# connect.net
KiCad netlist of a schematic drawn in Altium Designer
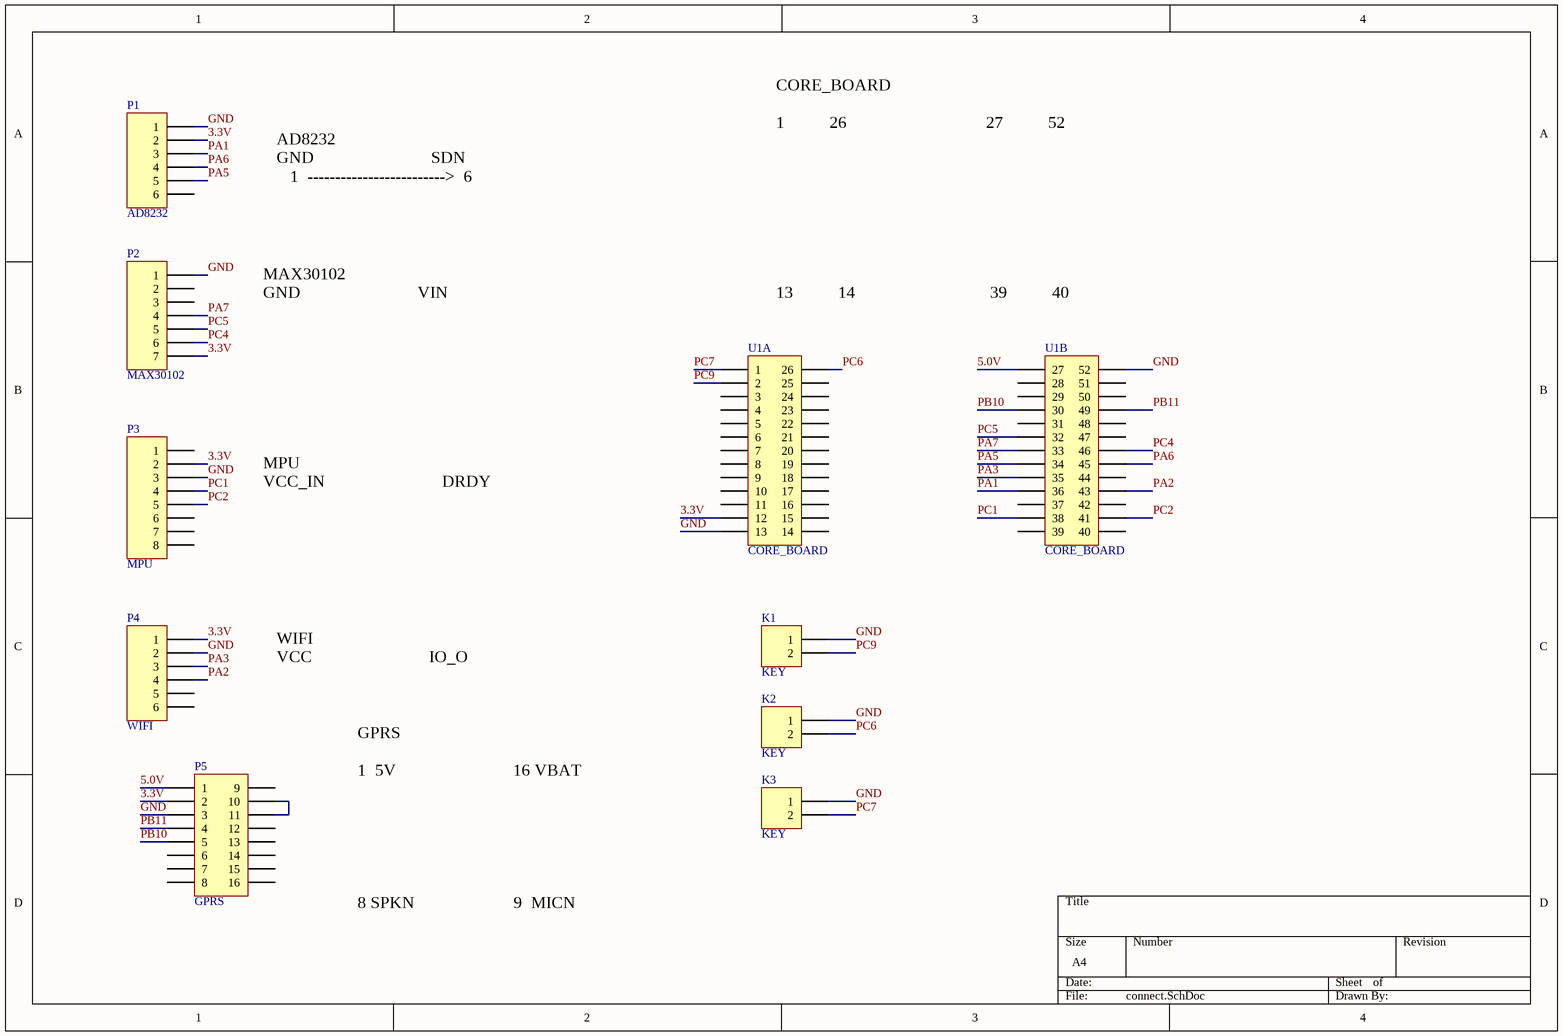
[diagram p0: connect.SchDoc]

(export (version "E")
  (design (tool "Eeschema 10.0.6"))
  (components
    (comp (ref "K1")
      (value "KEY")
      (footprint "KEY")
      (fields (field (name "PUBLISHER") "Altium Limited"))
      (libsource (lib "Schlib1") (part "KEY"))
    )
    (comp (ref "K2")
      (value "KEY")
      (footprint "KEY")
      (fields (field (name "PUBLISHER") "Altium Limited"))
      (libsource (lib "Schlib1") (part "KEY"))
    )
    (comp (ref "K3")
      (value "KEY")
      (footprint "KEY")
      (fields (field (name "PUBLISHER") "Altium Limited"))
      (libsource (lib "Schlib1") (part "KEY"))
    )
    (comp (ref "P1")
      (value "AD8232")
      (footprint "AD8232")
      (fields (field (name "PUBLISHER") "Altium Limited"))
      (libsource (lib "Schlib1") (part "AD8232"))
    )
    (comp (ref "P2")
      (value "MAX30102")
      (footprint "MAX30102")
      (fields (field (name "PUBLISHER") "Altium Limited"))
      (libsource (lib "Schlib1") (part "MAX30102"))
    )
    (comp (ref "P3")
      (value "MPU")
      (footprint "MPU")
      (fields (field (name "PUBLISHER") "Altium Limited"))
      (libsource (lib "Schlib1") (part "MPU"))
    )
    (comp (ref "P4")
      (value "WIFI")
      (footprint "WIFI")
      (fields (field (name "PUBLISHER") "Altium Limited"))
      (libsource (lib "Schlib1") (part "WIFI"))
    )
    (comp (ref "P5")
      (value "GPRS")
      (footprint "GPRS")
      (fields (field (name "PUBLISHER") "Altium Limited"))
      (libsource (lib "Schlib1") (part "GPRS"))
    )
    (comp (ref "U1")
      (value "CORE_BOARD")
      (footprint "CORE_BOARD")
      (libsource (lib "Schlib1") (part "CORE_BOARD"))
    )
  )
  (nets
    (net (code "1") (name "/3.3V") (class "Default")
      (node (ref "P1") (pin "2") (pinfunction "2_2") (pintype "passive"))
      (node (ref "P2") (pin "7") (pinfunction "7_7") (pintype "passive"))
      (node (ref "P3") (pin "2") (pinfunction "2_2") (pintype "passive"))
      (node (ref "P4") (pin "1") (pinfunction "1_1") (pintype "passive"))
      (node (ref "P5") (pin "2") (pinfunction "2_2") (pintype "passive"))
      (node (ref "U1") (pin "12") (pinfunction "12_12") (pintype "passive"))
    )
    (net (code "2") (name "/5.0V") (class "Default")
      (node (ref "P5") (pin "1") (pinfunction "1_1") (pintype "passive"))
      (node (ref "U1") (pin "27") (pinfunction "27_27") (pintype "passive"))
    )
    (net (code "3") (name "/GND") (class "Default")
      (node (ref "K1") (pin "1") (pinfunction "1_1") (pintype "passive"))
      (node (ref "K2") (pin "1") (pinfunction "1_1") (pintype "passive"))
      (node (ref "K3") (pin "1") (pinfunction "1_1") (pintype "passive"))
      (node (ref "P1") (pin "1") (pinfunction "1_1") (pintype "passive"))
      (node (ref "P2") (pin "1") (pinfunction "1_1") (pintype "passive"))
      (node (ref "P3") (pin "3") (pinfunction "3_3") (pintype "passive"))
      (node (ref "P4") (pin "2") (pinfunction "2_2") (pintype "passive"))
      (node (ref "P5") (pin "3") (pinfunction "3_3") (pintype "passive"))
      (node (ref "U1") (pin "13") (pinfunction "13_13") (pintype "passive"))
      (node (ref "U1") (pin "52") (pinfunction "52_52") (pintype "passive"))
    )
    (net (code "4") (name "/PA1") (class "Default")
      (node (ref "P1") (pin "3") (pinfunction "3_3") (pintype "passive"))
      (node (ref "U1") (pin "36") (pinfunction "36_36") (pintype "passive"))
    )
    (net (code "5") (name "/PA2") (class "Default")
      (node (ref "P4") (pin "4") (pinfunction "4_4") (pintype "passive"))
      (node (ref "U1") (pin "43") (pinfunction "43_43") (pintype "passive"))
    )
    (net (code "6") (name "/PA3") (class "Default")
      (node (ref "P4") (pin "3") (pinfunction "3_3") (pintype "passive"))
      (node (ref "U1") (pin "35") (pinfunction "35_35") (pintype "passive"))
    )
    (net (code "7") (name "/PA5") (class "Default")
      (node (ref "P1") (pin "5") (pinfunction "5_5") (pintype "passive"))
      (node (ref "U1") (pin "34") (pinfunction "34_34") (pintype "passive"))
    )
    (net (code "8") (name "/PA6") (class "Default")
      (node (ref "P1") (pin "4") (pinfunction "4_4") (pintype "passive"))
      (node (ref "U1") (pin "45") (pinfunction "45_45") (pintype "passive"))
    )
    (net (code "9") (name "/PA7") (class "Default")
      (node (ref "P2") (pin "4") (pinfunction "4_4") (pintype "passive"))
      (node (ref "U1") (pin "33") (pinfunction "33_33") (pintype "passive"))
    )
    (net (code "10") (name "/PB10") (class "Default")
      (node (ref "P5") (pin "5") (pinfunction "5_5") (pintype "passive"))
      (node (ref "U1") (pin "30") (pinfunction "30_30") (pintype "passive"))
    )
    (net (code "11") (name "/PB11") (class "Default")
      (node (ref "P5") (pin "4") (pinfunction "4_4") (pintype "passive"))
      (node (ref "U1") (pin "49") (pinfunction "49_49") (pintype "passive"))
    )
    (net (code "12") (name "/PC1") (class "Default")
      (node (ref "P3") (pin "4") (pinfunction "4_4") (pintype "passive"))
      (node (ref "U1") (pin "38") (pinfunction "38_38") (pintype "passive"))
    )
    (net (code "13") (name "/PC2") (class "Default")
      (node (ref "P3") (pin "5") (pinfunction "5_5") (pintype "passive"))
      (node (ref "U1") (pin "41") (pinfunction "41_41") (pintype "passive"))
    )
    (net (code "14") (name "/PC4") (class "Default")
      (node (ref "P2") (pin "6") (pinfunction "6_6") (pintype "passive"))
      (node (ref "U1") (pin "46") (pinfunction "46_46") (pintype "passive"))
    )
    (net (code "15") (name "/PC5") (class "Default")
      (node (ref "P2") (pin "5") (pinfunction "5_5") (pintype "passive"))
      (node (ref "U1") (pin "32") (pinfunction "32_32") (pintype "passive"))
    )
    (net (code "16") (name "/PC6") (class "Default")
      (node (ref "K2") (pin "2") (pinfunction "2_2") (pintype "passive"))
      (node (ref "U1") (pin "26") (pinfunction "26_26") (pintype "passive"))
    )
    (net (code "17") (name "/PC7") (class "Default")
      (node (ref "K3") (pin "2") (pinfunction "2_2") (pintype "passive"))
      (node (ref "U1") (pin "1") (pinfunction "1_1") (pintype "passive"))
    )
    (net (code "18") (name "/PC9") (class "Default")
      (node (ref "K1") (pin "2") (pinfunction "2_2") (pintype "passive"))
      (node (ref "U1") (pin "2") (pinfunction "2_2") (pintype "passive"))
    )
    (net (code "19") (name "Net-(P5-Pad10)") (class "Default")
      (node (ref "P5") (pin "10") (pinfunction "10_10") (pintype "passive"))
      (node (ref "P5") (pin "11") (pinfunction "11_11") (pintype "passive"))
    )
    (net (code "20") (name "unconnected-(P1-Pad6)") (class "Default")
      (node (ref "P1") (pin "6") (pinfunction "6_6") (pintype "passive"))
    )
    (net (code "21") (name "unconnected-(P2-Pad2)") (class "Default")
      (node (ref "P2") (pin "2") (pinfunction "2_2") (pintype "passive"))
    )
    (net (code "22") (name "unconnected-(P2-Pad3)") (class "Default")
      (node (ref "P2") (pin "3") (pinfunction "3_3") (pintype "passive"))
    )
    (net (code "23") (name "unconnected-(P3-Pad1)") (class "Default")
      (node (ref "P3") (pin "1") (pinfunction "1_1") (pintype "passive"))
    )
    (net (code "24") (name "unconnected-(P3-Pad6)") (class "Default")
      (node (ref "P3") (pin "6") (pinfunction "6_6") (pintype "passive"))
    )
    (net (code "25") (name "unconnected-(P3-Pad7)") (class "Default")
      (node (ref "P3") (pin "7") (pinfunction "7_7") (pintype "passive"))
    )
    (net (code "26") (name "unconnected-(P3-Pad8)") (class "Default")
      (node (ref "P3") (pin "8") (pinfunction "8_8") (pintype "passive"))
    )
    (net (code "27") (name "unconnected-(P4-Pad5)") (class "Default")
      (node (ref "P4") (pin "5") (pinfunction "5_5") (pintype "passive"))
    )
    (net (code "28") (name "unconnected-(P4-Pad6)") (class "Default")
      (node (ref "P4") (pin "6") (pinfunction "6_6") (pintype "passive"))
    )
    (net (code "29") (name "unconnected-(P5-Pad6)") (class "Default")
      (node (ref "P5") (pin "6") (pinfunction "6_6") (pintype "passive"))
    )
    (net (code "30") (name "unconnected-(P5-Pad7)") (class "Default")
      (node (ref "P5") (pin "7") (pinfunction "7_7") (pintype "passive"))
    )
    (net (code "31") (name "unconnected-(P5-Pad8)") (class "Default")
      (node (ref "P5") (pin "8") (pinfunction "8_8") (pintype "passive"))
    )
    (net (code "32") (name "unconnected-(P5-Pad9)") (class "Default")
      (node (ref "P5") (pin "9") (pinfunction "9_9") (pintype "passive"))
    )
    (net (code "33") (name "unconnected-(P5-Pad12)") (class "Default")
      (node (ref "P5") (pin "12") (pinfunction "12_12") (pintype "passive"))
    )
    (net (code "34") (name "unconnected-(P5-Pad13)") (class "Default")
      (node (ref "P5") (pin "13") (pinfunction "13_13") (pintype "passive"))
    )
    (net (code "35") (name "unconnected-(P5-Pad14)") (class "Default")
      (node (ref "P5") (pin "14") (pinfunction "14_14") (pintype "passive"))
    )
    (net (code "36") (name "unconnected-(P5-Pad15)") (class "Default")
      (node (ref "P5") (pin "15") (pinfunction "15_15") (pintype "passive"))
    )
    (net (code "37") (name "unconnected-(P5-Pad16)") (class "Default")
      (node (ref "P5") (pin "16") (pinfunction "16_16") (pintype "passive"))
    )
    (net (code "38") (name "unconnected-(U1-Pad3)") (class "Default")
      (node (ref "U1") (pin "3") (pinfunction "3_3") (pintype "passive"))
    )
    (net (code "39") (name "unconnected-(U1-Pad4)") (class "Default")
      (node (ref "U1") (pin "4") (pinfunction "4_4") (pintype "passive"))
    )
    (net (code "40") (name "unconnected-(U1-Pad5)") (class "Default")
      (node (ref "U1") (pin "5") (pinfunction "5_5") (pintype "passive"))
    )
    (net (code "41") (name "unconnected-(U1-Pad6)") (class "Default")
      (node (ref "U1") (pin "6") (pinfunction "6_6") (pintype "passive"))
    )
    (net (code "42") (name "unconnected-(U1-Pad7)") (class "Default")
      (node (ref "U1") (pin "7") (pinfunction "7_7") (pintype "passive"))
    )
    (net (code "43") (name "unconnected-(U1-Pad8)") (class "Default")
      (node (ref "U1") (pin "8") (pinfunction "8_8") (pintype "passive"))
    )
    (net (code "44") (name "unconnected-(U1-Pad9)") (class "Default")
      (node (ref "U1") (pin "9") (pinfunction "9_9") (pintype "passive"))
    )
    (net (code "45") (name "unconnected-(U1-Pad10)") (class "Default")
      (node (ref "U1") (pin "10") (pinfunction "10_10") (pintype "passive"))
    )
    (net (code "46") (name "unconnected-(U1-Pad11)") (class "Default")
      (node (ref "U1") (pin "11") (pinfunction "11_11") (pintype "passive"))
    )
    (net (code "47") (name "unconnected-(U1-Pad14)") (class "Default")
      (node (ref "U1") (pin "14") (pinfunction "14_14") (pintype "passive"))
    )
    (net (code "48") (name "unconnected-(U1-Pad15)") (class "Default")
      (node (ref "U1") (pin "15") (pinfunction "15_15") (pintype "passive"))
    )
    (net (code "49") (name "unconnected-(U1-Pad16)") (class "Default")
      (node (ref "U1") (pin "16") (pinfunction "16_16") (pintype "passive"))
    )
    (net (code "50") (name "unconnected-(U1-Pad17)") (class "Default")
      (node (ref "U1") (pin "17") (pinfunction "17_17") (pintype "passive"))
    )
    (net (code "51") (name "unconnected-(U1-Pad18)") (class "Default")
      (node (ref "U1") (pin "18") (pinfunction "18_18") (pintype "passive"))
    )
    (net (code "52") (name "unconnected-(U1-Pad19)") (class "Default")
      (node (ref "U1") (pin "19") (pinfunction "19_19") (pintype "passive"))
    )
    (net (code "53") (name "unconnected-(U1-Pad20)") (class "Default")
      (node (ref "U1") (pin "20") (pinfunction "20_20") (pintype "passive"))
    )
    (net (code "54") (name "unconnected-(U1-Pad21)") (class "Default")
      (node (ref "U1") (pin "21") (pinfunction "21_21") (pintype "passive"))
    )
    (net (code "55") (name "unconnected-(U1-Pad22)") (class "Default")
      (node (ref "U1") (pin "22") (pinfunction "22_22") (pintype "passive"))
    )
    (net (code "56") (name "unconnected-(U1-Pad23)") (class "Default")
      (node (ref "U1") (pin "23") (pinfunction "23_23") (pintype "passive"))
    )
    (net (code "57") (name "unconnected-(U1-Pad24)") (class "Default")
      (node (ref "U1") (pin "24") (pinfunction "24_24") (pintype "passive"))
    )
    (net (code "58") (name "unconnected-(U1-Pad25)") (class "Default")
      (node (ref "U1") (pin "25") (pinfunction "25_25") (pintype "passive"))
    )
    (net (code "59") (name "unconnected-(U1-Pad28)") (class "Default")
      (node (ref "U1") (pin "28") (pinfunction "28_28") (pintype "passive"))
    )
    (net (code "60") (name "unconnected-(U1-Pad29)") (class "Default")
      (node (ref "U1") (pin "29") (pinfunction "29_29") (pintype "passive"))
    )
    (net (code "61") (name "unconnected-(U1-Pad31)") (class "Default")
      (node (ref "U1") (pin "31") (pinfunction "31_31") (pintype "passive"))
    )
    (net (code "62") (name "unconnected-(U1-Pad37)") (class "Default")
      (node (ref "U1") (pin "37") (pinfunction "37_37") (pintype "passive"))
    )
    (net (code "63") (name "unconnected-(U1-Pad39)") (class "Default")
      (node (ref "U1") (pin "39") (pinfunction "39_39") (pintype "passive"))
    )
    (net (code "64") (name "unconnected-(U1-Pad40)") (class "Default")
      (node (ref "U1") (pin "40") (pinfunction "40_40") (pintype "passive"))
    )
    (net (code "65") (name "unconnected-(U1-Pad42)") (class "Default")
      (node (ref "U1") (pin "42") (pinfunction "42_42") (pintype "passive"))
    )
    (net (code "66") (name "unconnected-(U1-Pad44)") (class "Default")
      (node (ref "U1") (pin "44") (pinfunction "44_44") (pintype "passive"))
    )
    (net (code "67") (name "unconnected-(U1-Pad47)") (class "Default")
      (node (ref "U1") (pin "47") (pinfunction "47_47") (pintype "passive"))
    )
    (net (code "68") (name "unconnected-(U1-Pad48)") (class "Default")
      (node (ref "U1") (pin "48") (pinfunction "48_48") (pintype "passive"))
    )
    (net (code "69") (name "unconnected-(U1-Pad50)") (class "Default")
      (node (ref "U1") (pin "50") (pinfunction "50_50") (pintype "passive"))
    )
    (net (code "70") (name "unconnected-(U1-Pad51)") (class "Default")
      (node (ref "U1") (pin "51") (pinfunction "51_51") (pintype "passive"))
    )
  )
)
